# Seeeduino-v4_2.net
KiCad netlist of a schematic drawn in EAGLE
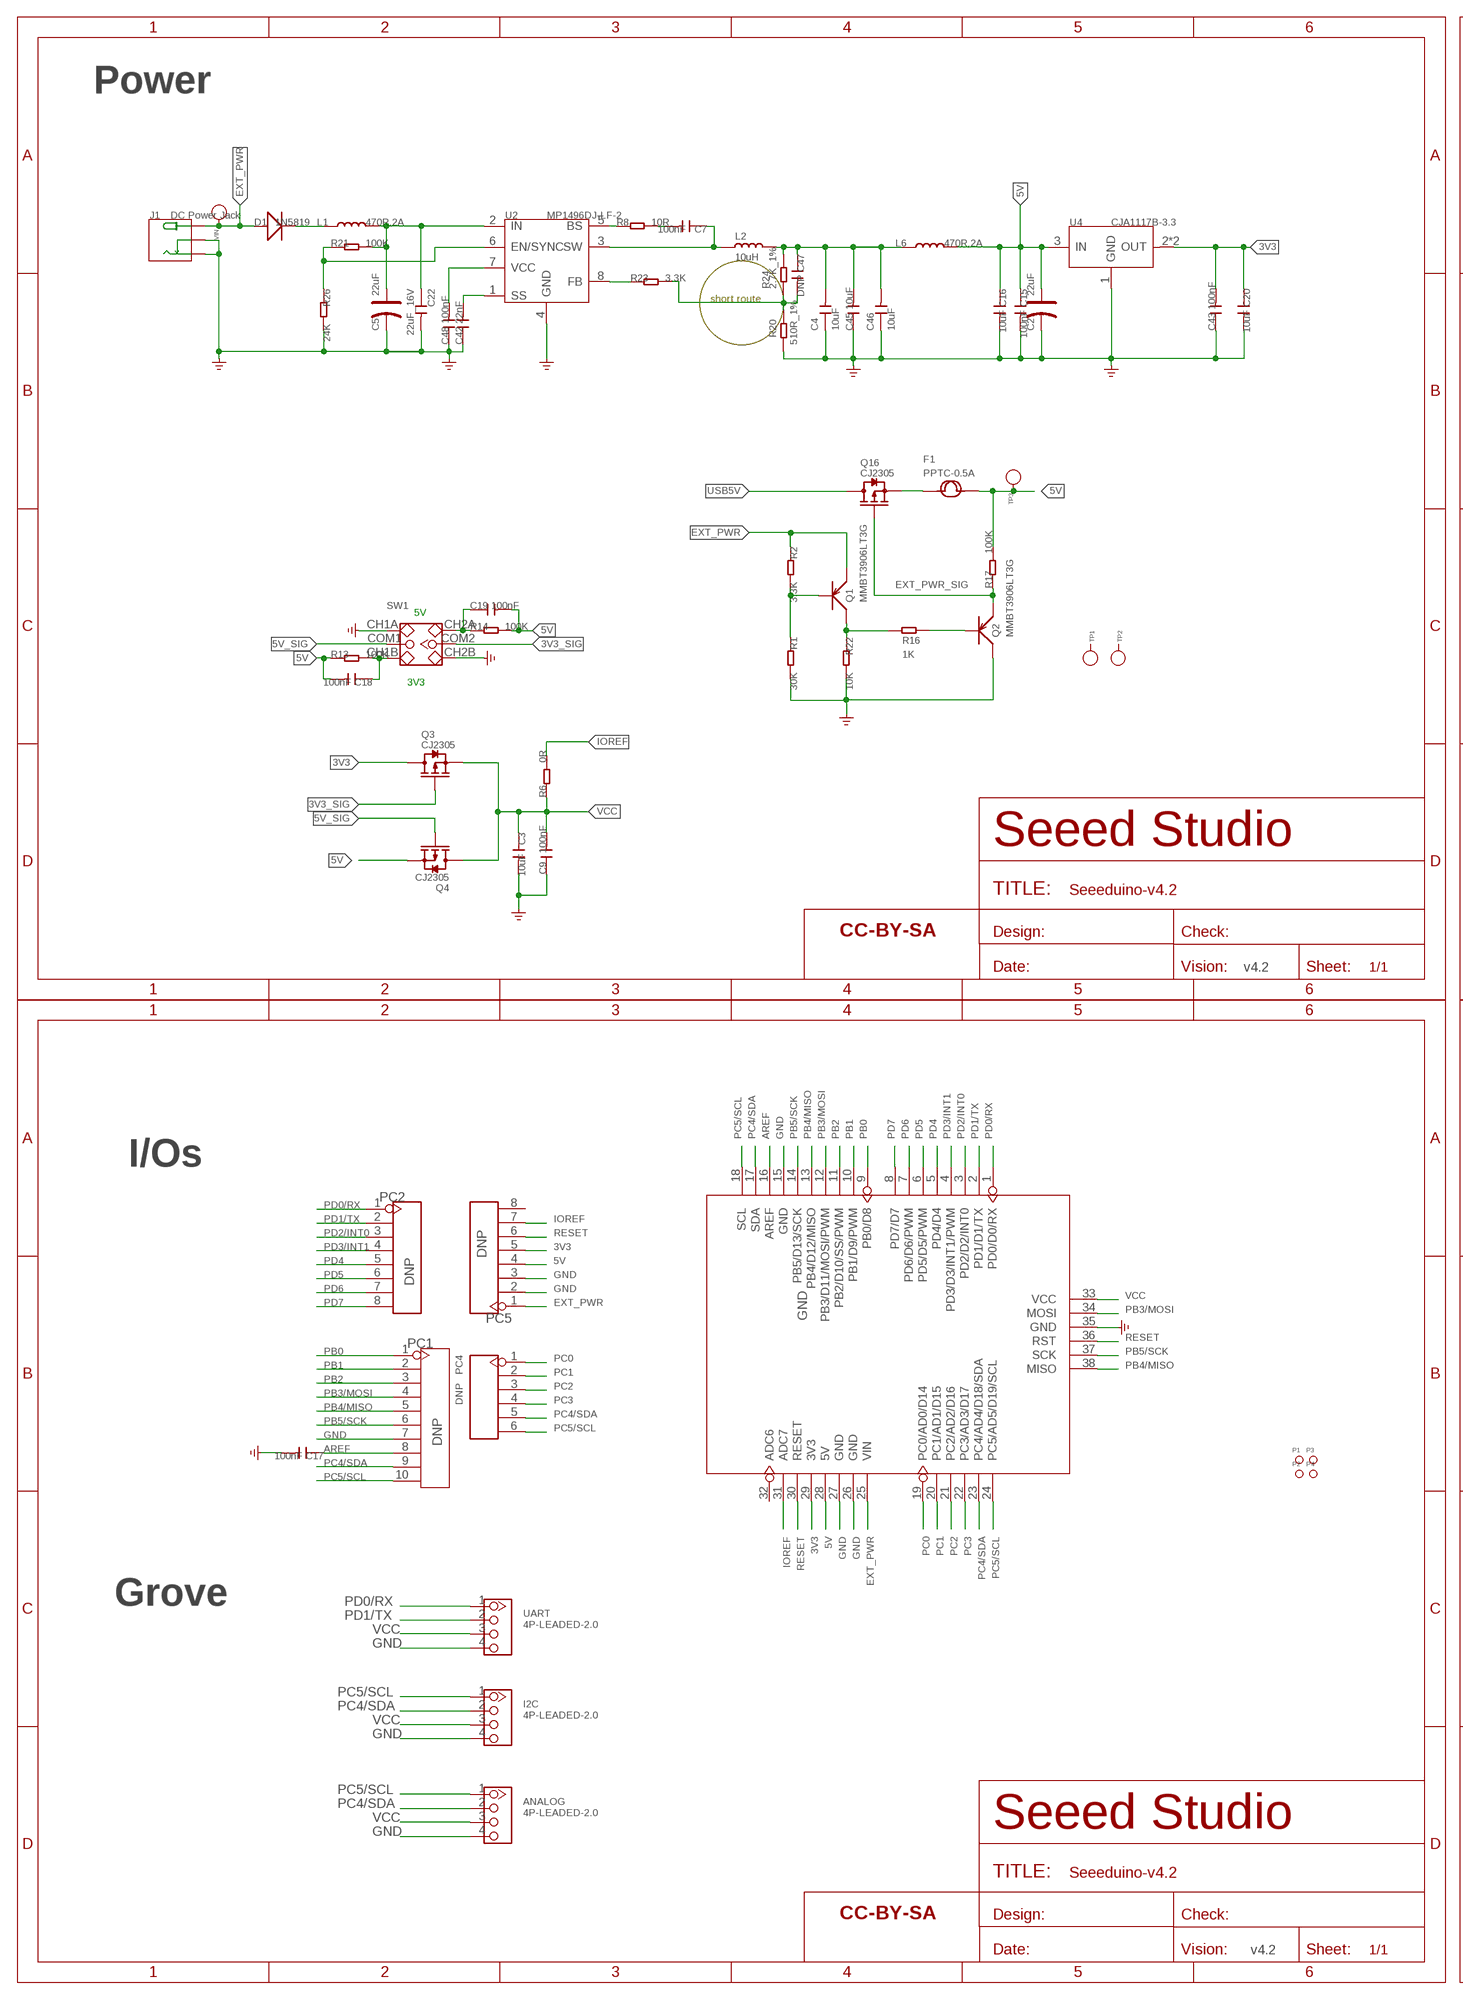
[diagram p0: schematic, sheet 1, part 1 of 2]
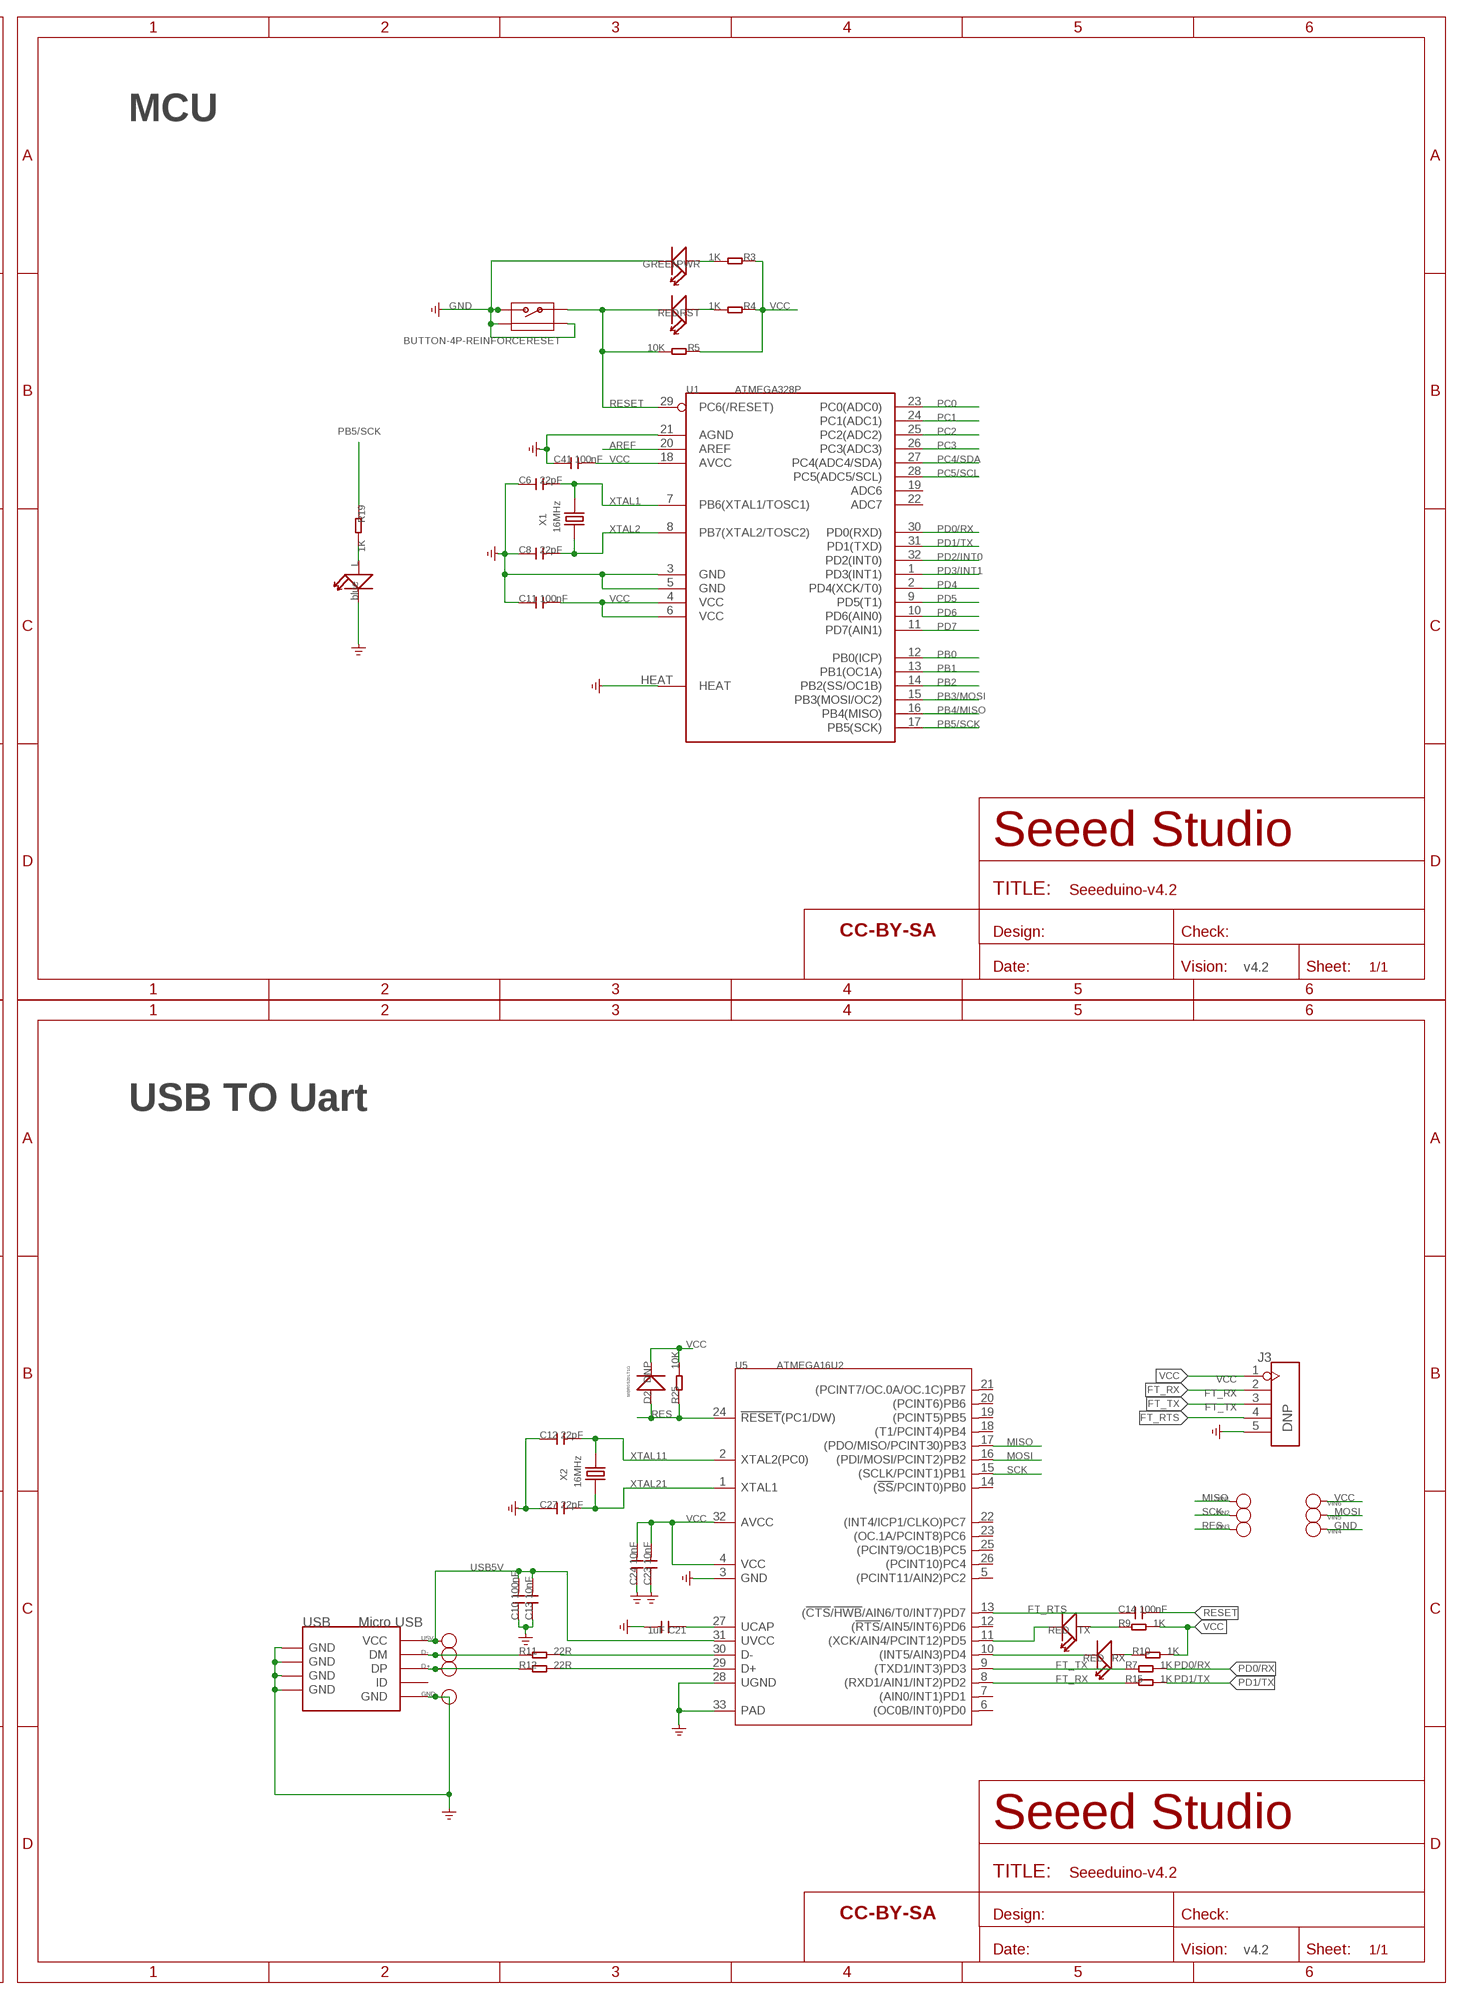
[diagram p1: schematic, sheet 1, part 2 of 2]

(export (version "E")
  (design (tool "Eeschema 10.0.6"))
  (components
    (comp (ref "ANALOG")
      (value "4P-LEADED-2.0")
      (footprint "eagle-import:4P-LEADED-2.0")
      (libsource (lib "eagle-import") (part "TWIG-2.0-LEADED"))
    )
    (comp (ref "C2")
      (value "22uF")
      (footprint "eagle-import:ELECTRO-SMD-B-4.8MM")
      (libsource (lib "eagle-import") (part "CAP-POLAR-ELECTRO-B"))
    )
    (comp (ref "C3")
      (value "10uF")
      (footprint "eagle-import:C0805")
      (libsource (lib "eagle-import") (part "C-0805"))
    )
    (comp (ref "C4")
      (value "10uF")
      (footprint "eagle-import:C0805")
      (libsource (lib "eagle-import") (part "CAP-0805"))
    )
    (comp (ref "C5")
      (value "22uF")
      (footprint "eagle-import:ELECTRO-SMD-B-4.8MM")
      (libsource (lib "eagle-import") (part "CAP-POLAR-ELECTRO-B"))
    )
    (comp (ref "C6")
      (value "22pF")
      (footprint "eagle-import:C0603")
      (libsource (lib "eagle-import") (part "C-0603"))
    )
    (comp (ref "C7")
      (value "100nF")
      (footprint "eagle-import:C0603")
      (libsource (lib "eagle-import") (part "C-0603"))
    )
    (comp (ref "C8")
      (value "22pF")
      (footprint "eagle-import:C0603")
      (libsource (lib "eagle-import") (part "C-0603"))
    )
    (comp (ref "C9")
      (value "100nF")
      (footprint "eagle-import:C0603")
      (libsource (lib "eagle-import") (part "C-0603"))
    )
    (comp (ref "C10")
      (value "100nF")
      (footprint "eagle-import:C0603")
      (libsource (lib "eagle-import") (part "C-0603"))
    )
    (comp (ref "C11")
      (value "100nF")
      (footprint "eagle-import:C0603")
      (libsource (lib "eagle-import") (part "C-0603"))
    )
    (comp (ref "C12")
      (value "22pF")
      (footprint "eagle-import:C0603")
      (libsource (lib "eagle-import") (part "C-0603"))
    )
    (comp (ref "C13")
      (value "10nF")
      (footprint "eagle-import:C0603")
      (libsource (lib "eagle-import") (part "C-0603"))
    )
    (comp (ref "C14")
      (value "100nF")
      (footprint "eagle-import:C0603")
      (libsource (lib "eagle-import") (part "C-0603"))
    )
    (comp (ref "C15")
      (value "100nF")
      (footprint "eagle-import:C0603")
      (libsource (lib "eagle-import") (part "C-0603"))
    )
    (comp (ref "C16")
      (value "10uF")
      (footprint "eagle-import:C0805")
      (libsource (lib "eagle-import") (part "C-0805"))
    )
    (comp (ref "C17")
      (value "100nF")
      (footprint "eagle-import:C0603")
      (libsource (lib "eagle-import") (part "C-0603"))
    )
    (comp (ref "C18")
      (value "100nF")
      (footprint "eagle-import:C0603")
      (libsource (lib "eagle-import") (part "C-0603"))
    )
    (comp (ref "C19")
      (value "100nF")
      (footprint "eagle-import:C0603")
      (libsource (lib "eagle-import") (part "C-0603"))
    )
    (comp (ref "C20")
      (value "10uF")
      (footprint "eagle-import:C0805")
      (libsource (lib "eagle-import") (part "C-0805"))
    )
    (comp (ref "C21")
      (value "1uF")
      (footprint "eagle-import:C0603")
      (libsource (lib "eagle-import") (part "C-0603"))
    )
    (comp (ref "C22")
      (value "22uF_16V")
      (footprint "eagle-import:C1206")
      (libsource (lib "eagle-import") (part "CAP-1206"))
    )
    (comp (ref "C23")
      (value "10nF")
      (footprint "eagle-import:C0603")
      (libsource (lib "eagle-import") (part "C-0603"))
    )
    (comp (ref "C24")
      (value "10nF")
      (footprint "eagle-import:C0603")
      (libsource (lib "eagle-import") (part "C-0603"))
    )
    (comp (ref "C27")
      (value "22pF")
      (footprint "eagle-import:C0603")
      (libsource (lib "eagle-import") (part "C-0603"))
    )
    (comp (ref "C41")
      (value "100nF")
      (footprint "eagle-import:C0603")
      (libsource (lib "eagle-import") (part "C-0603"))
    )
    (comp (ref "C42")
      (value "22nF")
      (footprint "eagle-import:C0603")
      (libsource (lib "eagle-import") (part "C-0603"))
    )
    (comp (ref "C43")
      (value "100nF")
      (footprint "eagle-import:C0603")
      (libsource (lib "eagle-import") (part "C-0603"))
    )
    (comp (ref "C45")
      (value "10uF")
      (footprint "eagle-import:C0805")
      (libsource (lib "eagle-import") (part "C-0805"))
    )
    (comp (ref "C46")
      (value "10uF")
      (footprint "eagle-import:C1206")
      (libsource (lib "eagle-import") (part "CAP-1206"))
    )
    (comp (ref "C47")
      (value "DNP")
      (footprint "eagle-import:C0603")
      (libsource (lib "eagle-import") (part "C-0603"))
    )
    (comp (ref "C48")
      (value "100nF")
      (footprint "eagle-import:C0603")
      (libsource (lib "eagle-import") (part "C-0603"))
    )
    (comp (ref "D+")
      (value "PAD-TEST-POINT'4545'")
      (footprint "eagle-import:TP_4545")
      (fields (field (name "PARTNO") "DNP"))
      (libsource (lib "eagle-import") (part "PAD-TEST-POINT'4545'"))
    )
    (comp (ref "D-")
      (value "PAD-TEST-POINT'4545'")
      (footprint "eagle-import:TP_4545")
      (fields (field (name "PARTNO") "DNP"))
      (libsource (lib "eagle-import") (part "PAD-TEST-POINT'4545'"))
    )
    (comp (ref "D1")
      (value "1N5819")
      (footprint "eagle-import:D2010")
      (libsource (lib "eagle-import") (part "D'DO-214AC'"))
    )
    (comp (ref "D2")
      (value "DNP")
      (footprint "eagle-import:SOD123")
      (libsource (lib "eagle-import") (part "D'1206'"))
    )
    (comp (ref "F1")
      (value "PPTC-0.5A")
      (footprint "eagle-import:F1206")
      (libsource (lib "eagle-import") (part "FUSE'1206'"))
    )
    (comp (ref "GND")
      (value "PAD-TEST-POINT'4545'")
      (footprint "eagle-import:TP_4545")
      (fields (field (name "PARTNO") "DNP"))
      (libsource (lib "eagle-import") (part "PAD-TEST-POINT'4545'"))
    )
    (comp (ref "I2C")
      (value "4P-LEADED-2.0")
      (footprint "eagle-import:4P-LEADED-2.0")
      (libsource (lib "eagle-import") (part "TWIG-2.0-LEADED"))
    )
    (comp (ref "J1")
      (value "DC Power Jack")
      (footprint "eagle-import:DC-404")
      (libsource (lib "eagle-import") (part "DC-044"))
    )
    (comp (ref "J3")
      (value "DNP")
      (footprint "eagle-import:5P-2.54")
      (libsource (lib "eagle-import") (part "HEADER-5P-2.54"))
    )
    (comp (ref "L")
      (value "blue")
      (footprint "eagle-import:LED-0603")
      (libsource (lib "eagle-import") (part "LED'0603'"))
    )
    (comp (ref "L1")
      (value "470R,2A")
      (footprint "eagle-import:L0805")
      (libsource (lib "eagle-import") (part "L'0805'"))
    )
    (comp (ref "L2")
      (value "10uH")
      (footprint "eagle-import:L5040S")
      (libsource (lib "eagle-import") (part "INDUCTOR/FERRITE-BEAD5040S"))
    )
    (comp (ref "L6")
      (value "470R,2A")
      (footprint "eagle-import:L0805")
      (libsource (lib "eagle-import") (part "L'0805'"))
    )
    (comp (ref "P1")
      (value "PAD-MARK")
      (footprint "eagle-import:ROUND-MARK-1.0")
      (fields (field (name "PARTNO") "DNP"))
      (libsource (lib "eagle-import") (part "PAD-MARK"))
    )
    (comp (ref "P2")
      (value "PAD-MARK")
      (footprint "eagle-import:ROUND-MARK-1.0")
      (fields (field (name "PARTNO") "DNP"))
      (libsource (lib "eagle-import") (part "PAD-MARK"))
    )
    (comp (ref "P3")
      (value "PAD-MARK")
      (footprint "eagle-import:ROUND-MARK-1.0")
      (fields (field (name "PARTNO") "DNP"))
      (libsource (lib "eagle-import") (part "PAD-MARK"))
    )
    (comp (ref "P4")
      (value "PAD-MARK")
      (footprint "eagle-import:ROUND-MARK-1.0")
      (fields (field (name "PARTNO") "DNP"))
      (libsource (lib "eagle-import") (part "PAD-MARK"))
    )
    (comp (ref "PC1")
      (value "DNP")
      (footprint "eagle-import:10P-2.54")
      (libsource (lib "eagle-import") (part "HEADER-10P-2.54"))
    )
    (comp (ref "PC2")
      (value "DNP")
      (footprint "eagle-import:8P-2.54")
      (libsource (lib "eagle-import") (part "HEADER-8P-2.54"))
    )
    (comp (ref "PC4")
      (value "DNP")
      (footprint "eagle-import:6P-2.54-65_35MIL")
      (libsource (lib "eagle-import") (part "HEADER-6P-65/35MIL"))
    )
    (comp (ref "PC5")
      (value "DNP")
      (footprint "eagle-import:8P-2.54")
      (libsource (lib "eagle-import") (part "HEADER-8P-2.54"))
    )
    (comp (ref "PWR")
      (value "GREEN")
      (footprint "eagle-import:LED-0603")
      (libsource (lib "eagle-import") (part "LED'0603'"))
    )
    (comp (ref "Q1")
      (value "MMBT3906LT3G")
      (footprint "eagle-import:SOT23")
      (libsource (lib "eagle-import") (part "TRANSISTOR-PNP-SOT23"))
    )
    (comp (ref "Q2")
      (value "MMBT3906LT3G")
      (footprint "eagle-import:SOT23")
      (libsource (lib "eagle-import") (part "TRANSISTOR-PNP-SOT23"))
    )
    (comp (ref "Q3")
      (value "CJ2305")
      (footprint "eagle-import:SOT23")
      (libsource (lib "eagle-import") (part "MOSFET-P'SI2323CDS/SI2305DS{lt}BR{gt}'"))
    )
    (comp (ref "Q4")
      (value "CJ2305")
      (footprint "eagle-import:SOT23")
      (libsource (lib "eagle-import") (part "MOSFET-P'SI2323CDS/SI2305DS{lt}BR{gt}'"))
    )
    (comp (ref "Q16")
      (value "CJ2305")
      (footprint "eagle-import:SOT23")
      (libsource (lib "eagle-import") (part "MOSFET-P'SI2323CDS/SI2305DS{lt}BR{gt}'"))
    )
    (comp (ref "R1")
      (value "30K")
      (footprint "eagle-import:R0603")
      (libsource (lib "eagle-import") (part "R-0603"))
    )
    (comp (ref "R2")
      (value "3.3K")
      (footprint "eagle-import:R0603")
      (libsource (lib "eagle-import") (part "R-0603"))
    )
    (comp (ref "R3")
      (value "1K")
      (footprint "eagle-import:R0603")
      (libsource (lib "eagle-import") (part "R-0603"))
    )
    (comp (ref "R4")
      (value "1K")
      (footprint "eagle-import:R0603")
      (libsource (lib "eagle-import") (part "R-0603"))
    )
    (comp (ref "R5")
      (value "10K")
      (footprint "eagle-import:R0603")
      (libsource (lib "eagle-import") (part "R-0603"))
    )
    (comp (ref "R6")
      (value "0R")
      (footprint "eagle-import:R0603")
      (libsource (lib "eagle-import") (part "R-0603"))
    )
    (comp (ref "R7")
      (value "1K")
      (footprint "eagle-import:R0603")
      (libsource (lib "eagle-import") (part "R-0603"))
    )
    (comp (ref "R8")
      (value "10R")
      (footprint "eagle-import:R0603")
      (libsource (lib "eagle-import") (part "R-0603"))
    )
    (comp (ref "R9")
      (value "1K")
      (footprint "eagle-import:R0603")
      (libsource (lib "eagle-import") (part "R-0603"))
    )
    (comp (ref "R10")
      (value "1K")
      (footprint "eagle-import:R0603")
      (libsource (lib "eagle-import") (part "R-0603"))
    )
    (comp (ref "R11")
      (value "22R")
      (footprint "eagle-import:R0603")
      (libsource (lib "eagle-import") (part "R-0603"))
    )
    (comp (ref "R12")
      (value "22R")
      (footprint "eagle-import:R0603")
      (libsource (lib "eagle-import") (part "R-0603"))
    )
    (comp (ref "R13")
      (value "100K")
      (footprint "eagle-import:R0603")
      (libsource (lib "eagle-import") (part "R-0603"))
    )
    (comp (ref "R14")
      (value "100K")
      (footprint "eagle-import:R0603")
      (libsource (lib "eagle-import") (part "R-0603"))
    )
    (comp (ref "R15")
      (value "1K")
      (footprint "eagle-import:R0603")
      (libsource (lib "eagle-import") (part "R-0603"))
    )
    (comp (ref "R16")
      (value "1K")
      (footprint "eagle-import:R0603")
      (libsource (lib "eagle-import") (part "R-0603"))
    )
    (comp (ref "R17")
      (value "100K")
      (footprint "eagle-import:R0603")
      (libsource (lib "eagle-import") (part "R-0603"))
    )
    (comp (ref "R19")
      (value "1K")
      (footprint "eagle-import:R0603")
      (libsource (lib "eagle-import") (part "R-0603"))
    )
    (comp (ref "R20")
      (value "510R_1%")
      (footprint "eagle-import:R0603")
      (libsource (lib "eagle-import") (part "R-0603"))
    )
    (comp (ref "R21")
      (value "100K")
      (footprint "eagle-import:R0603")
      (libsource (lib "eagle-import") (part "R-0603"))
    )
    (comp (ref "R22")
      (value "10K")
      (footprint "eagle-import:R0603")
      (libsource (lib "eagle-import") (part "R-0603"))
    )
    (comp (ref "R23")
      (value "3.3K")
      (footprint "eagle-import:R0603")
      (libsource (lib "eagle-import") (part "R-0603"))
    )
    (comp (ref "R24")
      (value "2.7K_1%")
      (footprint "eagle-import:R0603")
      (libsource (lib "eagle-import") (part "R-0603"))
    )
    (comp (ref "R25")
      (value "10K")
      (footprint "eagle-import:R0603")
      (libsource (lib "eagle-import") (part "R-0603"))
    )
    (comp (ref "R26")
      (value "24K")
      (footprint "eagle-import:R0603")
      (libsource (lib "eagle-import") (part "R-0603"))
    )
    (comp (ref "RESET")
      (value "BUTTON-4P-REINFORCE")
      (footprint "eagle-import:4P-SMD-7X3.5X3.5H")
      (libsource (lib "eagle-import") (part "BUTTON-4P-REINFORCE'TS-1188E'"))
    )
    (comp (ref "RST")
      (value "RED")
      (footprint "eagle-import:LED-0603")
      (libsource (lib "eagle-import") (part "LED'0603'"))
    )
    (comp (ref "RX")
      (value "RED")
      (footprint "eagle-import:LED-0603")
      (libsource (lib "eagle-import") (part "LED'0603'"))
    )
    (comp (ref "SW1")
      (value "SWITCH-2CH-6P-2.54")
      (footprint "eagle-import:6P-SMD-2CH-2.54-3.5X7.2")
      (libsource (lib "eagle-import") (part "SWITCH-2CH-6P-SMD"))
    )
    (comp (ref "TP1")
      (value "PAD-TEST-POINT'4545'")
      (footprint "eagle-import:TP_4545")
      (fields (field (name "PARTNO") "DNP"))
      (libsource (lib "eagle-import") (part "PAD-TEST-POINT'4545'"))
    )
    (comp (ref "TP2")
      (value "PAD-TEST-POINT'4545'")
      (footprint "eagle-import:TP_4545")
      (fields (field (name "PARTNO") "DNP"))
      (libsource (lib "eagle-import") (part "PAD-TEST-POINT'4545'"))
    )
    (comp (ref "TP3")
      (value "PAD-TEST-POINT'4545'")
      (footprint "eagle-import:TP_4545")
      (fields (field (name "PARTNO") "DNP"))
      (libsource (lib "eagle-import") (part "PAD-TEST-POINT'4545'"))
    )
    (comp (ref "TX")
      (value "RED")
      (footprint "eagle-import:LED-0603")
      (libsource (lib "eagle-import") (part "LED'0603'"))
    )
    (comp (ref "U$1")
      (value "SEEEDSTUDIO-OPEN-SCH-FRAME")
      (footprint "eagle-import:SEEEDSTUDIO-PCB-FRAME")
      (libsource (lib "eagle-import") (part "SEEEDSTUDIO-OPEN-SCH-FRAME"))
    )
    (comp (ref "U$6")
      (value "SEEEDSTUDIO-OPEN-SCH-FRAME")
      (footprint "eagle-import:SEEEDSTUDIO-PCB-FRAME")
      (libsource (lib "eagle-import") (part "SEEEDSTUDIO-OPEN-SCH-FRAME"))
    )
    (comp (ref "U$8")
      (value "SEEEDSTUDIO-OPEN-SCH-FRAME")
      (footprint "eagle-import:SEEEDSTUDIO-PCB-FRAME")
      (libsource (lib "eagle-import") (part "SEEEDSTUDIO-OPEN-SCH-FRAME"))
    )
    (comp (ref "U$23")
      (value "SEEEDSTUDIO-OPEN-SCH-FRAME")
      (footprint "eagle-import:SEEEDSTUDIO-PCB-FRAME")
      (libsource (lib "eagle-import") (part "SEEEDSTUDIO-OPEN-SCH-FRAME"))
    )
    (comp (ref "U1")
      (value "ATMEGA328P")
      (footprint "eagle-import:MLF32X")
      (libsource (lib "eagle-import") (part "MEGA8"))
    )
    (comp (ref "U2")
      (value "MP1496DJ-LF-2")
      (footprint "eagle-import:TSOT23-8")
      (libsource (lib "eagle-import") (part "MP1496DJ"))
    )
    (comp (ref "U3")
      (value "ARDUINO-38P")
      (footprint "eagle-import:ARDUINO-38P")
      (libsource (lib "eagle-import") (part "ARDUINO-38P"))
    )
    (comp (ref "U4")
      (value "CJA1117B-3.3")
      (footprint "eagle-import:SOT-89")
      (libsource (lib "eagle-import") (part "PMIC-CJ1117'SOT89'"))
    )
    (comp (ref "U5")
      (value "ATMEGA16U2")
      (footprint "eagle-import:QFN32")
      (libsource (lib "eagle-import") (part "ATMEGA16U2"))
    )
    (comp (ref "U5V")
      (value "PAD-TEST-POINT'4545'")
      (footprint "eagle-import:TP_4545")
      (fields (field (name "PARTNO") "DNP"))
      (libsource (lib "eagle-import") (part "PAD-TEST-POINT'4545'"))
    )
    (comp (ref "UART")
      (value "4P-LEADED-2.0")
      (footprint "eagle-import:4P-LEADED-2.0")
      (libsource (lib "eagle-import") (part "TWIG-2.0-LEADED"))
    )
    (comp (ref "USB")
      (value "Micro USB")
      (footprint "eagle-import:MICRO-USB")
      (libsource (lib "eagle-import") (part "USB-MINIUSB-5P-MICRO"))
    )
    (comp (ref "VIN")
      (value "PAD-TEST-POINT'4545'")
      (footprint "eagle-import:TP_4545")
      (fields (field (name "PARTNO") "DNP"))
      (libsource (lib "eagle-import") (part "PAD-TEST-POINT'4545'"))
    )
    (comp (ref "VIN1")
      (value "PAD-TEST-POINT'4545'")
      (footprint "eagle-import:TP_4545")
      (fields (field (name "PARTNO") "DNP"))
      (libsource (lib "eagle-import") (part "PAD-TEST-POINT'4545'"))
    )
    (comp (ref "VIN2")
      (value "PAD-TEST-POINT'4545'")
      (footprint "eagle-import:TP_4545")
      (fields (field (name "PARTNO") "DNP"))
      (libsource (lib "eagle-import") (part "PAD-TEST-POINT'4545'"))
    )
    (comp (ref "VIN3")
      (value "PAD-TEST-POINT'4545'")
      (footprint "eagle-import:TP_4545")
      (fields (field (name "PARTNO") "DNP"))
      (libsource (lib "eagle-import") (part "PAD-TEST-POINT'4545'"))
    )
    (comp (ref "VIN4")
      (value "PAD-TEST-POINT'4545'")
      (footprint "eagle-import:TP_4545")
      (fields (field (name "PARTNO") "DNP"))
      (libsource (lib "eagle-import") (part "PAD-TEST-POINT'4545'"))
    )
    (comp (ref "VIN5")
      (value "PAD-TEST-POINT'4545'")
      (footprint "eagle-import:TP_4545")
      (fields (field (name "PARTNO") "DNP"))
      (libsource (lib "eagle-import") (part "PAD-TEST-POINT'4545'"))
    )
    (comp (ref "VIN6")
      (value "PAD-TEST-POINT'4545'")
      (footprint "eagle-import:TP_4545")
      (fields (field (name "PARTNO") "DNP"))
      (libsource (lib "eagle-import") (part "PAD-TEST-POINT'4545'"))
    )
    (comp (ref "X1")
      (value "16MHz")
      (footprint "eagle-import:2P-SMD-5X3.2")
      (libsource (lib "eagle-import") (part "CRYSTAL'5032'"))
    )
    (comp (ref "X2")
      (value "16MHz")
      (footprint "eagle-import:2P-SMD-5X3.2")
      (libsource (lib "eagle-import") (part "CRYSTAL'5032'"))
    )
  )
  (nets
    (net (code "1") (name "/AREF") (class "Default")
      (node (ref "C17") (pin "1") (pinfunction "1_1") (pintype "passive"))
      (node (ref "PC1") (pin "8") (pinfunction "8_8") (pintype "bidirectional"))
      (node (ref "U1") (pin "20") (pinfunction "AREF_20") (pintype "bidirectional"))
      (node (ref "U3") (pin "16") (pinfunction "AREF_16") (pintype "bidirectional"))
    )
    (net (code "2") (name "/EXT_PWR_SIG") (class "Default")
      (node (ref "Q16") (pin "1") (pinfunction "G_1") (pintype "passive"))
      (node (ref "Q2") (pin "2") (pinfunction "E_2") (pintype "passive"))
      (node (ref "R17") (pin "1") (pinfunction "1_1") (pintype "passive"))
    )
    (net (code "3") (name "/MISO") (class "Default")
      (node (ref "U5") (pin "17") (pinfunction "(PDO/MISO/PCINT30)PB3_17") (pintype "bidirectional"))
      (node (ref "VIN1") (pin "T") (pinfunction "T_T") (pintype "bidirectional"))
    )
    (net (code "4") (name "/MOSI") (class "Default")
      (node (ref "U5") (pin "16") (pinfunction "(PDI/MOSI/PCINT2)PB2_16") (pintype "bidirectional"))
      (node (ref "VIN5") (pin "T") (pinfunction "T_T") (pintype "bidirectional"))
    )
    (net (code "5") (name "/PB0") (class "Default")
      (node (ref "PC1") (pin "1") (pinfunction "1_1") (pintype "bidirectional"))
      (node (ref "U1") (pin "12") (pinfunction "PB0(ICP)_12") (pintype "bidirectional"))
      (node (ref "U3") (pin "9") (pinfunction "PB0/D8_9") (pintype "bidirectional"))
    )
    (net (code "6") (name "/PB1") (class "Default")
      (node (ref "PC1") (pin "2") (pinfunction "2_2") (pintype "bidirectional"))
      (node (ref "U1") (pin "13") (pinfunction "PB1(OC1A)_13") (pintype "bidirectional"))
      (node (ref "U3") (pin "10") (pinfunction "PB1/D9/PWM_10") (pintype "bidirectional"))
    )
    (net (code "7") (name "/PB2") (class "Default")
      (node (ref "PC1") (pin "3") (pinfunction "3_3") (pintype "bidirectional"))
      (node (ref "U1") (pin "14") (pinfunction "PB2(SS/OC1B)_14") (pintype "bidirectional"))
      (node (ref "U3") (pin "11") (pinfunction "PB2/D10/SS/PWM_11") (pintype "bidirectional"))
    )
    (net (code "8") (name "/PB3{slash}MOSI") (class "Default")
      (node (ref "PC1") (pin "4") (pinfunction "4_4") (pintype "bidirectional"))
      (node (ref "U1") (pin "15") (pinfunction "PB3(MOSI/OC2)_15") (pintype "bidirectional"))
      (node (ref "U3") (pin "12") (pinfunction "PB3/D11/MOSI/PWM_12") (pintype "bidirectional"))
      (node (ref "U3") (pin "34") (pinfunction "MOSI_34") (pintype "bidirectional"))
    )
    (net (code "9") (name "/PB4{slash}MISO") (class "Default")
      (node (ref "PC1") (pin "5") (pinfunction "5_5") (pintype "bidirectional"))
      (node (ref "U1") (pin "16") (pinfunction "PB4(MISO)_16") (pintype "bidirectional"))
      (node (ref "U3") (pin "13") (pinfunction "PB4/D12/MISO_13") (pintype "bidirectional"))
      (node (ref "U3") (pin "38") (pinfunction "MISO_38") (pintype "bidirectional"))
    )
    (net (code "10") (name "/PB5{slash}SCK") (class "Default")
      (node (ref "PC1") (pin "6") (pinfunction "6_6") (pintype "bidirectional"))
      (node (ref "R19") (pin "1") (pinfunction "1_1") (pintype "passive"))
      (node (ref "U1") (pin "17") (pinfunction "PB5(SCK)_17") (pintype "bidirectional"))
      (node (ref "U3") (pin "14") (pinfunction "PB5/D13/SCK_14") (pintype "bidirectional"))
      (node (ref "U3") (pin "37") (pinfunction "SCK_37") (pintype "bidirectional"))
    )
    (net (code "11") (name "/PC0") (class "Default")
      (node (ref "PC4") (pin "1") (pinfunction "1_1") (pintype "bidirectional"))
      (node (ref "U1") (pin "23") (pinfunction "PC0(ADC0)_23") (pintype "bidirectional"))
      (node (ref "U3") (pin "19") (pinfunction "PC0/AD0/D14_19") (pintype "bidirectional"))
    )
    (net (code "12") (name "/PC1") (class "Default")
      (node (ref "PC4") (pin "2") (pinfunction "2_2") (pintype "bidirectional"))
      (node (ref "U1") (pin "24") (pinfunction "PC1(ADC1)_24") (pintype "bidirectional"))
      (node (ref "U3") (pin "20") (pinfunction "PC1/AD1/D15_20") (pintype "bidirectional"))
    )
    (net (code "13") (name "/PC2") (class "Default")
      (node (ref "PC4") (pin "3") (pinfunction "3_3") (pintype "bidirectional"))
      (node (ref "U1") (pin "25") (pinfunction "PC2(ADC2)_25") (pintype "bidirectional"))
      (node (ref "U3") (pin "21") (pinfunction "PC2/AD2/D16_21") (pintype "bidirectional"))
    )
    (net (code "14") (name "/PC3") (class "Default")
      (node (ref "PC4") (pin "4") (pinfunction "4_4") (pintype "bidirectional"))
      (node (ref "U1") (pin "26") (pinfunction "PC3(ADC3)_26") (pintype "bidirectional"))
      (node (ref "U3") (pin "22") (pinfunction "PC3/AD3/D17_22") (pintype "bidirectional"))
    )
    (net (code "15") (name "/PC4{slash}SDA") (class "Default")
      (node (ref "ANALOG") (pin "2") (pinfunction "2_2") (pintype "bidirectional"))
      (node (ref "I2C") (pin "2") (pinfunction "2_2") (pintype "bidirectional"))
      (node (ref "PC1") (pin "9") (pinfunction "9_9") (pintype "bidirectional"))
      (node (ref "PC4") (pin "5") (pinfunction "5_5") (pintype "bidirectional"))
      (node (ref "U1") (pin "27") (pinfunction "PC4(ADC4/SDA)_27") (pintype "bidirectional"))
      (node (ref "U3") (pin "17") (pinfunction "SDA_17") (pintype "bidirectional"))
      (node (ref "U3") (pin "23") (pinfunction "PC4/AD4/D18/SDA_23") (pintype "bidirectional"))
    )
    (net (code "16") (name "/PC5{slash}SCL") (class "Default")
      (node (ref "ANALOG") (pin "1") (pinfunction "1_1") (pintype "bidirectional"))
      (node (ref "I2C") (pin "1") (pinfunction "1_1") (pintype "bidirectional"))
      (node (ref "PC1") (pin "10") (pinfunction "10_10") (pintype "bidirectional"))
      (node (ref "PC4") (pin "6") (pinfunction "6_6") (pintype "bidirectional"))
      (node (ref "U1") (pin "28") (pinfunction "PC5(ADC5/SCL)_28") (pintype "bidirectional"))
      (node (ref "U3") (pin "18") (pinfunction "SCL_18") (pintype "bidirectional"))
      (node (ref "U3") (pin "24") (pinfunction "PC5/AD5/D19/SCL_24") (pintype "bidirectional"))
    )
    (net (code "17") (name "/PD2{slash}INT0") (class "Default")
      (node (ref "PC2") (pin "3") (pinfunction "3_3") (pintype "bidirectional"))
      (node (ref "U1") (pin "32") (pinfunction "PD2(INT0)_32") (pintype "bidirectional"))
      (node (ref "U3") (pin "3") (pinfunction "PD2/D2/INT0_3") (pintype "bidirectional"))
    )
    (net (code "18") (name "/PD3{slash}INT1") (class "Default")
      (node (ref "PC2") (pin "4") (pinfunction "4_4") (pintype "bidirectional"))
      (node (ref "U1") (pin "1") (pinfunction "PD3(INT1)_1") (pintype "bidirectional"))
      (node (ref "U3") (pin "4") (pinfunction "PD3/D3/INT1/PWM_4") (pintype "bidirectional"))
    )
    (net (code "19") (name "/PD4") (class "Default")
      (node (ref "PC2") (pin "5") (pinfunction "5_5") (pintype "bidirectional"))
      (node (ref "U1") (pin "2") (pinfunction "PD4(XCK/T0)_2") (pintype "bidirectional"))
      (node (ref "U3") (pin "5") (pinfunction "PD4/D4_5") (pintype "bidirectional"))
    )
    (net (code "20") (name "/PD5") (class "Default")
      (node (ref "PC2") (pin "6") (pinfunction "6_6") (pintype "bidirectional"))
      (node (ref "U1") (pin "9") (pinfunction "PD5(T1)_9") (pintype "bidirectional"))
      (node (ref "U3") (pin "6") (pinfunction "PD5/D5/PWM_6") (pintype "bidirectional"))
    )
    (net (code "21") (name "/PD6") (class "Default")
      (node (ref "PC2") (pin "7") (pinfunction "7_7") (pintype "bidirectional"))
      (node (ref "U1") (pin "10") (pinfunction "PD6(AIN0)_10") (pintype "bidirectional"))
      (node (ref "U3") (pin "7") (pinfunction "PD6/D6/PWM_7") (pintype "bidirectional"))
    )
    (net (code "22") (name "/PD7") (class "Default")
      (node (ref "PC2") (pin "8") (pinfunction "8_8") (pintype "bidirectional"))
      (node (ref "U1") (pin "11") (pinfunction "PD7(AIN1)_11") (pintype "bidirectional"))
      (node (ref "U3") (pin "8") (pinfunction "PD7/D7_8") (pintype "bidirectional"))
    )
    (net (code "23") (name "/RES") (class "Default")
      (node (ref "D2") (pin "+") (pinfunction "+_+") (pintype "passive"))
      (node (ref "R25") (pin "1") (pinfunction "1_1") (pintype "passive"))
      (node (ref "U5") (pin "24") (pinfunction "~{RESET}(PC1/DW)_24") (pintype "bidirectional"))
      (node (ref "VIN3") (pin "T") (pinfunction "T_T") (pintype "bidirectional"))
    )
    (net (code "24") (name "/SCK") (class "Default")
      (node (ref "U5") (pin "15") (pinfunction "(SCLK/PCINT1)PB1_15") (pintype "bidirectional"))
      (node (ref "VIN2") (pin "T") (pinfunction "T_T") (pintype "bidirectional"))
    )
    (net (code "25") (name "/XTAL1") (class "Default")
      (node (ref "C6") (pin "2") (pinfunction "2_2") (pintype "passive"))
      (node (ref "U1") (pin "7") (pinfunction "PB6(XTAL1/TOSC1)_7") (pintype "bidirectional"))
      (node (ref "X1") (pin "2") (pinfunction "2_2") (pintype "passive"))
    )
    (net (code "26") (name "/XTAL2") (class "Default")
      (node (ref "C8") (pin "2") (pinfunction "2_2") (pintype "passive"))
      (node (ref "U1") (pin "8") (pinfunction "PB7(XTAL2/TOSC2)_8") (pintype "bidirectional"))
      (node (ref "X1") (pin "1") (pinfunction "1_1") (pintype "passive"))
    )
    (net (code "27") (name "/XTAL11") (class "Default")
      (node (ref "C12") (pin "2") (pinfunction "2_2") (pintype "passive"))
      (node (ref "U5") (pin "2") (pinfunction "XTAL2(PC0)_2") (pintype "bidirectional"))
      (node (ref "X2") (pin "2") (pinfunction "2_2") (pintype "passive"))
    )
    (net (code "28") (name "/XTAL21") (class "Default")
      (node (ref "C27") (pin "2") (pinfunction "2_2") (pintype "passive"))
      (node (ref "U5") (pin "1") (pinfunction "XTAL1_1") (pintype "bidirectional"))
      (node (ref "X2") (pin "1") (pinfunction "1_1") (pintype "passive"))
    )
    (net (code "29") (name "3V3") (class "Default")
      (node (ref "C20") (pin "1") (pinfunction "1_1") (pintype "passive"))
      (node (ref "C43") (pin "2") (pinfunction "2_2") (pintype "passive"))
      (node (ref "PC5") (pin "5") (pinfunction "5_5") (pintype "bidirectional"))
      (node (ref "Q3") (pin "3") (pinfunction "D_3") (pintype "passive"))
      (node (ref "U3") (pin "29") (pinfunction "3V3_29") (pintype "bidirectional"))
      (node (ref "U4") (pin "2") (pinfunction "OUT_2") (pintype "bidirectional"))
      (node (ref "U4") (pin "4") (pinfunction "OUT_4") (pintype "bidirectional"))
    )
    (net (code "30") (name "3V3_SIG") (class "Default")
      (node (ref "Q3") (pin "1") (pinfunction "G_1") (pintype "passive"))
      (node (ref "SW1") (pin "COM2") (pinfunction "COM2_COM2") (pintype "bidirectional"))
    )
    (net (code "31") (name "5V") (class "Default")
      (node (ref "C15") (pin "1") (pinfunction "1_1") (pintype "passive"))
      (node (ref "C16") (pin "1") (pinfunction "1_1") (pintype "passive"))
      (node (ref "C18") (pin "2") (pinfunction "2_2") (pintype "passive"))
      (node (ref "C19") (pin "2") (pinfunction "2_2") (pintype "passive"))
      (node (ref "C2") (pin "+") (pinfunction "+_+") (pintype "passive"))
      (node (ref "F1") (pin "2") (pinfunction "2_2") (pintype "bidirectional"))
      (node (ref "L6") (pin "2") (pinfunction "2_2") (pintype "passive"))
      (node (ref "PC5") (pin "4") (pinfunction "4_4") (pintype "bidirectional"))
      (node (ref "Q4") (pin "2") (pinfunction "S_2") (pintype "passive"))
      (node (ref "R13") (pin "1") (pinfunction "1_1") (pintype "passive"))
      (node (ref "R14") (pin "2") (pinfunction "2_2") (pintype "passive"))
      (node (ref "R17") (pin "2") (pinfunction "2_2") (pintype "passive"))
      (node (ref "TP3") (pin "T") (pinfunction "T_T") (pintype "bidirectional"))
      (node (ref "U3") (pin "28") (pinfunction "5V_28") (pintype "bidirectional"))
      (node (ref "U4") (pin "3") (pinfunction "IN_3") (pintype "bidirectional"))
    )
    (net (code "32") (name "5V_SIG") (class "Default")
      (node (ref "Q4") (pin "1") (pinfunction "G_1") (pintype "passive"))
      (node (ref "SW1") (pin "COM1") (pinfunction "COM1_COM1") (pintype "bidirectional"))
    )
    (net (code "33") (name "EXT_PWR") (class "Default")
      (node (ref "D1") (pin "+") (pinfunction "+_+") (pintype "passive"))
      (node (ref "J1") (pin "+") (pinfunction "+_+") (pintype "bidirectional"))
      (node (ref "PC5") (pin "1") (pinfunction "1_1") (pintype "bidirectional"))
      (node (ref "Q1") (pin "2") (pinfunction "E_2") (pintype "passive"))
      (node (ref "R2") (pin "1") (pinfunction "1_1") (pintype "passive"))
      (node (ref "U3") (pin "25") (pinfunction "VIN_25") (pintype "bidirectional"))
      (node (ref "VIN") (pin "T") (pinfunction "T_T") (pintype "bidirectional"))
    )
    (net (code "34") (name "FT_RTS") (class "Default")
      (node (ref "C14") (pin "1") (pinfunction "1_1") (pintype "passive"))
      (node (ref "J3") (pin "4") (pinfunction "4_4") (pintype "bidirectional"))
      (node (ref "U5") (pin "13") (pinfunction "(~{CTS}/~{HWB}/AIN6/T0/INT7)PD7_13") (pintype "bidirectional"))
    )
    (net (code "35") (name "FT_RX") (class "Default")
      (node (ref "J3") (pin "2") (pinfunction "2_2") (pintype "bidirectional"))
      (node (ref "R15") (pin "1") (pinfunction "1_1") (pintype "passive"))
      (node (ref "U5") (pin "8") (pinfunction "(RXD1/AIN1/INT2)PD2_8") (pintype "bidirectional"))
    )
    (net (code "36") (name "FT_TX") (class "Default")
      (node (ref "J3") (pin "3") (pinfunction "3_3") (pintype "bidirectional"))
      (node (ref "R7") (pin "1") (pinfunction "1_1") (pintype "passive"))
      (node (ref "U5") (pin "9") (pinfunction "(TXD1/INT3)PD3_9") (pintype "bidirectional"))
    )
    (net (code "37") (name "GND_POWER") (class "Default")
      (node (ref "ANALOG") (pin "4") (pinfunction "4_4") (pintype "bidirectional"))
      (node (ref "C10") (pin "1") (pinfunction "1_1") (pintype "passive"))
      (node (ref "C11") (pin "1") (pinfunction "1_1") (pintype "passive"))
      (node (ref "C12") (pin "1") (pinfunction "1_1") (pintype "passive"))
      (node (ref "C13") (pin "1") (pinfunction "1_1") (pintype "passive"))
      (node (ref "C15") (pin "2") (pinfunction "2_2") (pintype "passive"))
      (node (ref "C16") (pin "2") (pinfunction "2_2") (pintype "passive"))
      (node (ref "C17") (pin "2") (pinfunction "2_2") (pintype "passive"))
      (node (ref "C2") (pin "-") (pinfunction "-_-") (pintype "passive"))
      (node (ref "C20") (pin "2") (pinfunction "2_2") (pintype "passive"))
      (node (ref "C21") (pin "2") (pinfunction "2_2") (pintype "passive"))
      (node (ref "C22") (pin "2") (pinfunction "2_2") (pintype "passive"))
      (node (ref "C23") (pin "1") (pinfunction "1_1") (pintype "passive"))
      (node (ref "C24") (pin "1") (pinfunction "1_1") (pintype "passive"))
      (node (ref "C27") (pin "1") (pinfunction "1_1") (pintype "passive"))
      (node (ref "C3") (pin "2") (pinfunction "2_2") (pintype "passive"))
      (node (ref "C4") (pin "1") (pinfunction "1_1") (pintype "passive"))
      (node (ref "C41") (pin "1") (pinfunction "1_1") (pintype "passive"))
      (node (ref "C42") (pin "1") (pinfunction "1_1") (pintype "passive"))
      (node (ref "C43") (pin "1") (pinfunction "1_1") (pintype "passive"))
      (node (ref "C45") (pin "1") (pinfunction "1_1") (pintype "passive"))
      (node (ref "C46") (pin "1") (pinfunction "1_1") (pintype "passive"))
      (node (ref "C48") (pin "1") (pinfunction "1_1") (pintype "passive"))
      (node (ref "C5") (pin "-") (pinfunction "-_-") (pintype "passive"))
      (node (ref "C6") (pin "1") (pinfunction "1_1") (pintype "passive"))
      (node (ref "C8") (pin "1") (pinfunction "1_1") (pintype "passive"))
      (node (ref "C9") (pin "1") (pinfunction "1_1") (pintype "passive"))
      (node (ref "GND") (pin "T") (pinfunction "T_T") (pintype "bidirectional"))
      (node (ref "I2C") (pin "4") (pinfunction "4_4") (pintype "bidirectional"))
      (node (ref "J1") (pin "-") (pinfunction "-_-") (pintype "bidirectional"))
      (node (ref "J1") (pin "CDN") (pinfunction "CDN_CDN") (pintype "bidirectional"))
      (node (ref "J3") (pin "5") (pinfunction "5_5") (pintype "bidirectional"))
      (node (ref "L") (pin "-") (pinfunction "-_-") (pintype "passive"))
      (node (ref "PC1") (pin "7") (pinfunction "7_7") (pintype "bidirectional"))
      (node (ref "PC5") (pin "2") (pinfunction "2_2") (pintype "bidirectional"))
      (node (ref "PC5") (pin "3") (pinfunction "3_3") (pintype "bidirectional"))
      (node (ref "PWR") (pin "-") (pinfunction "-_-") (pintype "passive"))
      (node (ref "Q2") (pin "3") (pinfunction "C_3") (pintype "passive"))
      (node (ref "R1") (pin "2") (pinfunction "2_2") (pintype "passive"))
      (node (ref "R20") (pin "1") (pinfunction "1_1") (pintype "passive"))
      (node (ref "R22") (pin "2") (pinfunction "2_2") (pintype "passive"))
      (node (ref "R26") (pin "2") (pinfunction "2_2") (pintype "passive"))
      (node (ref "RESET") (pin "2") (pinfunction "2_2") (pintype "bidirectional"))
      (node (ref "RESET") (pin "S1") (pinfunction "S1_S1") (pintype "bidirectional"))
      (node (ref "RESET") (pin "S2") (pinfunction "S2_S2") (pintype "bidirectional"))
      (node (ref "SW1") (pin "CH1A") (pinfunction "CH1A_CH1A") (pintype "bidirectional"))
      (node (ref "SW1") (pin "CH2B") (pinfunction "CH2B_CH2B") (pintype "bidirectional"))
      (node (ref "U1") (pin "21") (pinfunction "AGND_21") (pintype "bidirectional"))
      (node (ref "U1") (pin "3") (pinfunction "GND_3") (pintype "bidirectional"))
      (node (ref "U1") (pin "5") (pinfunction "GND_5") (pintype "bidirectional"))
      (node (ref "U1") (pin "HEAT") (pinfunction "HEAT_HEAT") (pintype "bidirectional"))
      (node (ref "U2") (pin "4") (pinfunction "GND_4") (pintype "bidirectional"))
      (node (ref "U3") (pin "15") (pinfunction "GND_15") (pintype "bidirectional"))
      (node (ref "U3") (pin "26") (pinfunction "GND_26") (pintype "bidirectional"))
      (node (ref "U3") (pin "27") (pinfunction "GND_27") (pintype "bidirectional"))
      (node (ref "U3") (pin "35") (pinfunction "GND_35") (pintype "bidirectional"))
      (node (ref "U4") (pin "1") (pinfunction "GND_1") (pintype "bidirectional"))
      (node (ref "U5") (pin "28") (pinfunction "UGND_28") (pintype "bidirectional"))
      (node (ref "U5") (pin "3") (pinfunction "GND_3") (pintype "bidirectional"))
      (node (ref "U5") (pin "33") (pinfunction "PAD_33") (pintype "bidirectional"))
      (node (ref "UART") (pin "4") (pinfunction "4_4") (pintype "bidirectional"))
      (node (ref "USB") (pin "5") (pinfunction "GND_5") (pintype "bidirectional"))
      (node (ref "USB") (pin "S1") (pinfunction "GND_S1") (pintype "bidirectional"))
      (node (ref "USB") (pin "S2") (pinfunction "GND_S2") (pintype "bidirectional"))
      (node (ref "USB") (pin "S3") (pinfunction "GND_S3") (pintype "bidirectional"))
      (node (ref "USB") (pin "S4") (pinfunction "GND_S4") (pintype "bidirectional"))
      (node (ref "USB") (pin "S5") (pinfunction "GND_S5") (pintype "bidirectional"))
      (node (ref "USB") (pin "S6") (pinfunction "GND_S6") (pintype "bidirectional"))
      (node (ref "VIN4") (pin "T") (pinfunction "T_T") (pintype "bidirectional"))
    )
    (net (code "38") (name "IOREF") (class "Default")
      (node (ref "PC5") (pin "7") (pinfunction "7_7") (pintype "bidirectional"))
      (node (ref "R6") (pin "2") (pinfunction "2_2") (pintype "passive"))
      (node (ref "U3") (pin "31") (pinfunction "ADC7_31") (pintype "bidirectional"))
    )
    (net (code "39") (name "Net-(C4-Pad2)") (class "Default")
      (node (ref "C4") (pin "2") (pinfunction "2_2") (pintype "passive"))
      (node (ref "C45") (pin "2") (pinfunction "2_2") (pintype "passive"))
      (node (ref "C46") (pin "2") (pinfunction "2_2") (pintype "passive"))
      (node (ref "C47") (pin "1") (pinfunction "1_1") (pintype "passive"))
      (node (ref "L2") (pin "2") (pinfunction "2_2") (pintype "passive"))
      (node (ref "L6") (pin "1") (pinfunction "1_1") (pintype "passive"))
      (node (ref "R24") (pin "1") (pinfunction "1_1") (pintype "passive"))
    )
    (net (code "40") (name "Net-(C7-Pad2)") (class "Default")
      (node (ref "C7") (pin "2") (pinfunction "2_2") (pintype "passive"))
      (node (ref "R8") (pin "2") (pinfunction "2_2") (pintype "passive"))
    )
    (net (code "41") (name "Net-(C18-Pad1)") (class "Default")
      (node (ref "C18") (pin "1") (pinfunction "1_1") (pintype "passive"))
      (node (ref "R13") (pin "2") (pinfunction "2_2") (pintype "passive"))
      (node (ref "SW1") (pin "CH1B") (pinfunction "CH1B_CH1B") (pintype "bidirectional"))
    )
    (net (code "42") (name "Net-(C19-Pad1)") (class "Default")
      (node (ref "C19") (pin "1") (pinfunction "1_1") (pintype "passive"))
      (node (ref "R14") (pin "1") (pinfunction "1_1") (pintype "passive"))
      (node (ref "SW1") (pin "CH2A") (pinfunction "CH2A_CH2A") (pintype "bidirectional"))
    )
    (net (code "43") (name "Net-(C47-Pad2)") (class "Default")
      (node (ref "C47") (pin "2") (pinfunction "2_2") (pintype "passive"))
      (node (ref "R20") (pin "2") (pinfunction "2_2") (pintype "passive"))
      (node (ref "R23") (pin "2") (pinfunction "2_2") (pintype "passive"))
      (node (ref "R24") (pin "2") (pinfunction "2_2") (pintype "passive"))
    )
    (net (code "44") (name "Net-(D1-Pad-)") (class "Default")
      (node (ref "D1") (pin "-") (pinfunction "-_-") (pintype "passive"))
      (node (ref "L1") (pin "1") (pinfunction "1_1") (pintype "passive"))
    )
    (net (code "45") (name "Net-(L-Pad+)") (class "Default")
      (node (ref "L") (pin "+") (pinfunction "+_+") (pintype "passive"))
      (node (ref "R19") (pin "2") (pinfunction "2_2") (pintype "passive"))
    )
    (net (code "46") (name "Net-(PWR-Pad+)") (class "Default")
      (node (ref "PWR") (pin "+") (pinfunction "+_+") (pintype "passive"))
      (node (ref "R3") (pin "2") (pinfunction "2_2") (pintype "passive"))
    )
    (net (code "47") (name "Net-(Q1-B)") (class "Default")
      (node (ref "Q1") (pin "1") (pinfunction "B_1") (pintype "passive"))
      (node (ref "R1") (pin "1") (pinfunction "1_1") (pintype "passive"))
      (node (ref "R2") (pin "2") (pinfunction "2_2") (pintype "passive"))
    )
    (net (code "48") (name "Net-(Q1-C)") (class "Default")
      (node (ref "Q1") (pin "3") (pinfunction "C_3") (pintype "passive"))
      (node (ref "R16") (pin "1") (pinfunction "1_1") (pintype "passive"))
      (node (ref "R22") (pin "1") (pinfunction "1_1") (pintype "passive"))
    )
    (net (code "49") (name "Net-(Q2-B)") (class "Default")
      (node (ref "Q2") (pin "1") (pinfunction "B_1") (pintype "passive"))
      (node (ref "R16") (pin "2") (pinfunction "2_2") (pintype "passive"))
    )
    (net (code "50") (name "Net-(Q16-S)") (class "Default")
      (node (ref "F1") (pin "1") (pinfunction "1_1") (pintype "bidirectional"))
      (node (ref "Q16") (pin "2") (pinfunction "S_2") (pintype "passive"))
    )
    (net (code "51") (name "Net-(R4-Pad2)") (class "Default")
      (node (ref "R4") (pin "2") (pinfunction "2_2") (pintype "passive"))
      (node (ref "RST") (pin "+") (pinfunction "+_+") (pintype "passive"))
    )
    (net (code "52") (name "Net-(R9-Pad1)") (class "Default")
      (node (ref "R9") (pin "1") (pinfunction "1_1") (pintype "passive"))
      (node (ref "TX") (pin "+") (pinfunction "+_+") (pintype "passive"))
    )
    (net (code "53") (name "Net-(R10-Pad1)") (class "Default")
      (node (ref "R10") (pin "1") (pinfunction "1_1") (pintype "passive"))
      (node (ref "RX") (pin "+") (pinfunction "+_+") (pintype "passive"))
    )
    (net (code "54") (name "Net-(U2-BS)") (class "Default")
      (node (ref "R8") (pin "1") (pinfunction "1_1") (pintype "passive"))
      (node (ref "U2") (pin "5") (pinfunction "BS_5") (pintype "bidirectional"))
    )
    (net (code "55") (name "Net-(U2-EN{slash}SYNC)") (class "Default")
      (node (ref "R21") (pin "1") (pinfunction "1_1") (pintype "passive"))
      (node (ref "R26") (pin "1") (pinfunction "1_1") (pintype "passive"))
      (node (ref "U2") (pin "6") (pinfunction "EN/SYNC_6") (pintype "bidirectional"))
    )
    (net (code "56") (name "Net-(U2-FB)") (class "Default")
      (node (ref "R23") (pin "1") (pinfunction "1_1") (pintype "passive"))
      (node (ref "U2") (pin "8") (pinfunction "FB_8") (pintype "bidirectional"))
    )
    (net (code "57") (name "Net-(U2-IN)") (class "Default")
      (node (ref "C22") (pin "1") (pinfunction "1_1") (pintype "passive"))
      (node (ref "C5") (pin "+") (pinfunction "+_+") (pintype "passive"))
      (node (ref "L1") (pin "2") (pinfunction "2_2") (pintype "passive"))
      (node (ref "R21") (pin "2") (pinfunction "2_2") (pintype "passive"))
      (node (ref "U2") (pin "2") (pinfunction "IN_2") (pintype "bidirectional"))
    )
    (net (code "58") (name "Net-(U2-SS)") (class "Default")
      (node (ref "C42") (pin "2") (pinfunction "2_2") (pintype "passive"))
      (node (ref "U2") (pin "1") (pinfunction "SS_1") (pintype "bidirectional"))
    )
    (net (code "59") (name "Net-(U2-SW)") (class "Default")
      (node (ref "C7") (pin "1") (pinfunction "1_1") (pintype "passive"))
      (node (ref "L2") (pin "1") (pinfunction "1_1") (pintype "passive"))
      (node (ref "U2") (pin "3") (pinfunction "SW_3") (pintype "bidirectional"))
    )
    (net (code "60") (name "Net-(U2-VCC)") (class "Default")
      (node (ref "C48") (pin "2") (pinfunction "2_2") (pintype "passive"))
      (node (ref "U2") (pin "7") (pinfunction "VCC_7") (pintype "bidirectional"))
    )
    (net (code "61") (name "Net-(U5-(INT5{slash}AIN3)PD4)") (class "Default")
      (node (ref "RX") (pin "-") (pinfunction "-_-") (pintype "passive"))
      (node (ref "U5") (pin "10") (pinfunction "(INT5/AIN3)PD4_10") (pintype "bidirectional"))
    )
    (net (code "62") (name "Net-(U5-(XCK{slash}AIN4{slash}PCINT12)PD5)") (class "Default")
      (node (ref "TX") (pin "-") (pinfunction "-_-") (pintype "passive"))
      (node (ref "U5") (pin "11") (pinfunction "(XCK/AIN4/PCINT12)PD5_11") (pintype "bidirectional"))
    )
    (net (code "63") (name "Net-(U5-D+)") (class "Default")
      (node (ref "R12") (pin "2") (pinfunction "2_2") (pintype "passive"))
      (node (ref "U5") (pin "29") (pinfunction "D+_29") (pintype "bidirectional"))
    )
    (net (code "64") (name "Net-(U5-D-)") (class "Default")
      (node (ref "R11") (pin "2") (pinfunction "2_2") (pintype "passive"))
      (node (ref "U5") (pin "30") (pinfunction "D-_30") (pintype "bidirectional"))
    )
    (net (code "65") (name "Net-(U5-UCAP)") (class "Default")
      (node (ref "C21") (pin "1") (pinfunction "1_1") (pintype "passive"))
      (node (ref "U5") (pin "27") (pinfunction "UCAP_27") (pintype "bidirectional"))
    )
    (net (code "66") (name "Net-(USB-DM)") (class "Default")
      (node (ref "D-") (pin "T") (pinfunction "T_T") (pintype "bidirectional"))
      (node (ref "R11") (pin "1") (pinfunction "1_1") (pintype "passive"))
      (node (ref "USB") (pin "2") (pinfunction "DM_2") (pintype "bidirectional"))
    )
    (net (code "67") (name "Net-(USB-DP)") (class "Default")
      (node (ref "D+") (pin "T") (pinfunction "T_T") (pintype "bidirectional"))
      (node (ref "R12") (pin "1") (pinfunction "1_1") (pintype "passive"))
      (node (ref "USB") (pin "3") (pinfunction "DP_3") (pintype "bidirectional"))
    )
    (net (code "68") (name "PD0{slash}RX") (class "Default")
      (node (ref "PC2") (pin "1") (pinfunction "1_1") (pintype "bidirectional"))
      (node (ref "R7") (pin "2") (pinfunction "2_2") (pintype "passive"))
      (node (ref "U1") (pin "30") (pinfunction "PD0(RXD)_30") (pintype "bidirectional"))
      (node (ref "U3") (pin "1") (pinfunction "PD0/D0/RX_1") (pintype "bidirectional"))
      (node (ref "UART") (pin "1") (pinfunction "1_1") (pintype "bidirectional"))
    )
    (net (code "69") (name "PD1{slash}TX") (class "Default")
      (node (ref "PC2") (pin "2") (pinfunction "2_2") (pintype "bidirectional"))
      (node (ref "R15") (pin "2") (pinfunction "2_2") (pintype "passive"))
      (node (ref "U1") (pin "31") (pinfunction "PD1(TXD)_31") (pintype "bidirectional"))
      (node (ref "U3") (pin "2") (pinfunction "PD1/D1/TX_2") (pintype "bidirectional"))
      (node (ref "UART") (pin "2") (pinfunction "2_2") (pintype "bidirectional"))
    )
    (net (code "70") (name "RESET") (class "Default")
      (node (ref "C14") (pin "2") (pinfunction "2_2") (pintype "passive"))
      (node (ref "PC5") (pin "6") (pinfunction "6_6") (pintype "bidirectional"))
      (node (ref "R5") (pin "2") (pinfunction "2_2") (pintype "passive"))
      (node (ref "RESET") (pin "1") (pinfunction "1_1") (pintype "bidirectional"))
      (node (ref "RST") (pin "-") (pinfunction "-_-") (pintype "passive"))
      (node (ref "U1") (pin "29") (pinfunction "PC6(/RESET)_29") (pintype "bidirectional"))
      (node (ref "U3") (pin "30") (pinfunction "RESET_30") (pintype "bidirectional"))
      (node (ref "U3") (pin "36") (pinfunction "RST_36") (pintype "bidirectional"))
    )
    (net (code "71") (name "USB5V") (class "Default")
      (node (ref "C10") (pin "2") (pinfunction "2_2") (pintype "passive"))
      (node (ref "C13") (pin "2") (pinfunction "2_2") (pintype "passive"))
      (node (ref "Q16") (pin "3") (pinfunction "D_3") (pintype "passive"))
      (node (ref "U5") (pin "31") (pinfunction "UVCC_31") (pintype "bidirectional"))
      (node (ref "U5V") (pin "T") (pinfunction "T_T") (pintype "bidirectional"))
      (node (ref "USB") (pin "1") (pinfunction "VCC_1") (pintype "bidirectional"))
    )
    (net (code "72") (name "VCC") (class "Default")
      (node (ref "ANALOG") (pin "3") (pinfunction "3_3") (pintype "bidirectional"))
      (node (ref "C11") (pin "2") (pinfunction "2_2") (pintype "passive"))
      (node (ref "C23") (pin "2") (pinfunction "2_2") (pintype "passive"))
      (node (ref "C24") (pin "2") (pinfunction "2_2") (pintype "passive"))
      (node (ref "C3") (pin "1") (pinfunction "1_1") (pintype "passive"))
      (node (ref "C41") (pin "2") (pinfunction "2_2") (pintype "passive"))
      (node (ref "C9") (pin "2") (pinfunction "2_2") (pintype "passive"))
      (node (ref "D2") (pin "-") (pinfunction "-_-") (pintype "passive"))
      (node (ref "I2C") (pin "3") (pinfunction "3_3") (pintype "bidirectional"))
      (node (ref "J3") (pin "1") (pinfunction "1_1") (pintype "bidirectional"))
      (node (ref "Q3") (pin "2") (pinfunction "S_2") (pintype "passive"))
      (node (ref "Q4") (pin "3") (pinfunction "D_3") (pintype "passive"))
      (node (ref "R10") (pin "2") (pinfunction "2_2") (pintype "passive"))
      (node (ref "R25") (pin "2") (pinfunction "2_2") (pintype "passive"))
      (node (ref "R3") (pin "1") (pinfunction "1_1") (pintype "passive"))
      (node (ref "R4") (pin "1") (pinfunction "1_1") (pintype "passive"))
      (node (ref "R5") (pin "1") (pinfunction "1_1") (pintype "passive"))
      (node (ref "R6") (pin "1") (pinfunction "1_1") (pintype "passive"))
      (node (ref "R9") (pin "2") (pinfunction "2_2") (pintype "passive"))
      (node (ref "U1") (pin "18") (pinfunction "AVCC_18") (pintype "bidirectional"))
      (node (ref "U1") (pin "4") (pinfunction "VCC_4") (pintype "bidirectional"))
      (node (ref "U1") (pin "6") (pinfunction "VCC_6") (pintype "bidirectional"))
      (node (ref "U3") (pin "33") (pinfunction "VCC_33") (pintype "bidirectional"))
      (node (ref "U5") (pin "32") (pinfunction "AVCC_32") (pintype "bidirectional"))
      (node (ref "U5") (pin "4") (pinfunction "VCC_4") (pintype "bidirectional"))
      (node (ref "UART") (pin "3") (pinfunction "3_3") (pintype "bidirectional"))
      (node (ref "VIN6") (pin "T") (pinfunction "T_T") (pintype "bidirectional"))
    )
    (net (code "73") (name "unconnected-(PC5-Pad8)") (class "Default")
      (node (ref "PC5") (pin "8") (pinfunction "8_8") (pintype "bidirectional"))
    )
    (net (code "74") (name "unconnected-(TP1-PadT)") (class "Default")
      (node (ref "TP1") (pin "T") (pinfunction "T_T") (pintype "bidirectional"))
    )
    (net (code "75") (name "unconnected-(TP2-PadT)") (class "Default")
      (node (ref "TP2") (pin "T") (pinfunction "T_T") (pintype "bidirectional"))
    )
    (net (code "76") (name "unconnected-(U1-ADC6-Pad19)") (class "Default")
      (node (ref "U1") (pin "19") (pinfunction "ADC6_19") (pintype "bidirectional"))
    )
    (net (code "77") (name "unconnected-(U1-ADC7-Pad22)") (class "Default")
      (node (ref "U1") (pin "22") (pinfunction "ADC7_22") (pintype "bidirectional"))
    )
    (net (code "78") (name "unconnected-(U3-ADC6-Pad32)") (class "Default")
      (node (ref "U3") (pin "32") (pinfunction "ADC6_32") (pintype "bidirectional"))
    )
    (net (code "79") (name "unconnected-(U5-(AIN0{slash}INT1)PD1-Pad7)") (class "Default")
      (node (ref "U5") (pin "7") (pinfunction "(AIN0/INT1)PD1_7") (pintype "bidirectional"))
    )
    (net (code "80") (name "unconnected-(U5-(INT4{slash}ICP1{slash}CLKO)PC7-Pad22)") (class "Default")
      (node (ref "U5") (pin "22") (pinfunction "(INT4/ICP1/CLKO)PC7_22") (pintype "bidirectional"))
    )
    (net (code "81") (name "unconnected-(U5-(OC.1A{slash}PCINT8)PC6-Pad23)") (class "Default")
      (node (ref "U5") (pin "23") (pinfunction "(OC.1A/PCINT8)PC6_23") (pintype "bidirectional"))
    )
    (net (code "82") (name "unconnected-(U5-(OC0B{slash}INT0)PD0-Pad6)") (class "Default")
      (node (ref "U5") (pin "6") (pinfunction "(OC0B/INT0)PD0_6") (pintype "bidirectional"))
    )
    (net (code "83") (name "unconnected-(U5-(PCINT5)PB5-Pad19)") (class "Default")
      (node (ref "U5") (pin "19") (pinfunction "(PCINT5)PB5_19") (pintype "bidirectional"))
    )
    (net (code "84") (name "unconnected-(U5-(PCINT6)PB6-Pad20)") (class "Default")
      (node (ref "U5") (pin "20") (pinfunction "(PCINT6)PB6_20") (pintype "bidirectional"))
    )
    (net (code "85") (name "unconnected-(U5-(PCINT7{slash}OC.0A{slash}OC.1C)PB7-Pad21)") (class "Default")
      (node (ref "U5") (pin "21") (pinfunction "(PCINT7/OC.0A/OC.1C)PB7_21") (pintype "bidirectional"))
    )
    (net (code "86") (name "unconnected-(U5-(PCINT9{slash}OC1B)PC5-Pad25)") (class "Default")
      (node (ref "U5") (pin "25") (pinfunction "(PCINT9/OC1B)PC5_25") (pintype "bidirectional"))
    )
    (net (code "87") (name "unconnected-(U5-(PCINT10)PC4-Pad26)") (class "Default")
      (node (ref "U5") (pin "26") (pinfunction "(PCINT10)PC4_26") (pintype "bidirectional"))
    )
    (net (code "88") (name "unconnected-(U5-(PCINT11{slash}AIN2)PC2-Pad5)") (class "Default")
      (node (ref "U5") (pin "5") (pinfunction "(PCINT11/AIN2)PC2_5") (pintype "bidirectional"))
    )
    (net (code "89") (name "unconnected-(U5-(T1{slash}PCINT4)PB4-Pad18)") (class "Default")
      (node (ref "U5") (pin "18") (pinfunction "(T1/PCINT4)PB4_18") (pintype "bidirectional"))
    )
    (net (code "90") (name "unconnected-(U5-(~{RTS}{slash}AIN5{slash}INT6)PD6-Pad12)") (class "Default")
      (node (ref "U5") (pin "12") (pinfunction "(~{RTS}/AIN5/INT6)PD6_12") (pintype "bidirectional"))
    )
    (net (code "91") (name "unconnected-(U5-(~{SS}{slash}PCINT0)PB0-Pad14)") (class "Default")
      (node (ref "U5") (pin "14") (pinfunction "(~{SS}/PCINT0)PB0_14") (pintype "bidirectional"))
    )
    (net (code "92") (name "unconnected-(USB-ID-Pad4)") (class "Default")
      (node (ref "USB") (pin "4") (pinfunction "ID_4") (pintype "bidirectional"))
    )
  )
)
